# Shield.net
KiCad netlist of a schematic drawn in EAGLE
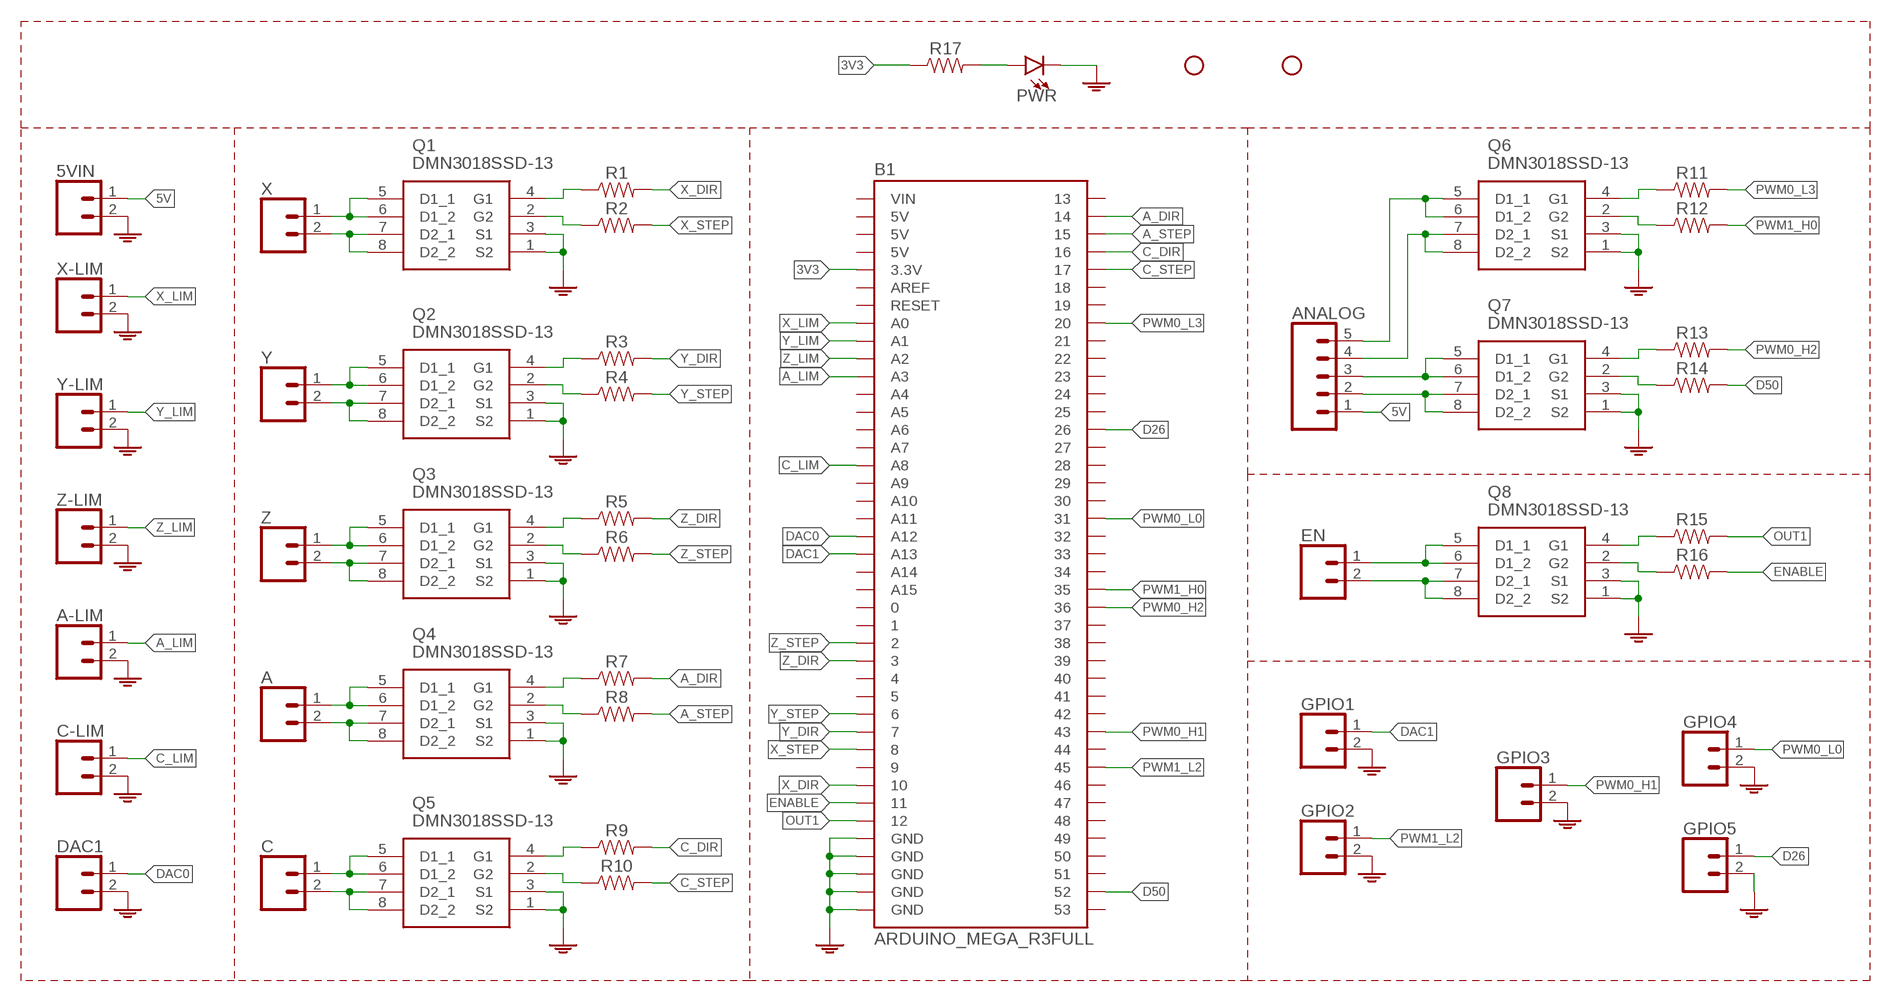
[diagram p0: schematic, sheet 1]

(export (version "E")
  (design (tool "Eeschema 10.0.6"))
  (components
    (comp (ref "5VIN")
      (value "2P-SCREWTERMINAL-PLUGABLE")
      (footprint "eagle-import:SCREWTERMINAL-3.5MM-2_LOCK")
      (libsource (lib "eagle-import") (part "2P-SCREWTERMINAL-PLUGABLE"))
    )
    (comp (ref "A")
      (value "2P-SCREWTERMINAL-PLUGABLE")
      (footprint "eagle-import:SCREWTERMINAL-3.5MM-2_LOCK")
      (libsource (lib "eagle-import") (part "2P-SCREWTERMINAL-PLUGABLE"))
    )
    (comp (ref "A-LIM")
      (value "2P-SCREWTERMINAL-PLUGABLE")
      (footprint "eagle-import:SCREWTERMINAL-3.5MM-2_LOCK")
      (libsource (lib "eagle-import") (part "2P-SCREWTERMINAL-PLUGABLE"))
    )
    (comp (ref "ANALOG")
      (value "JST-XH-5P")
      (footprint "eagle-import:JST-XH-5P")
      (libsource (lib "eagle-import") (part "JST-XH-5P"))
    )
    (comp (ref "B1")
      (value "ARDUINO_MEGA_R3FULL")
      (footprint "eagle-import:ARDUINO_MEGA")
      (libsource (lib "eagle-import") (part "ARDUINO_MEGA_R3FULL"))
    )
    (comp (ref "C")
      (value "2P-SCREWTERMINAL-PLUGABLE")
      (footprint "eagle-import:SCREWTERMINAL-3.5MM-2_LOCK")
      (libsource (lib "eagle-import") (part "2P-SCREWTERMINAL-PLUGABLE"))
    )
    (comp (ref "C-LIM")
      (value "2P-SCREWTERMINAL-PLUGABLE")
      (footprint "eagle-import:SCREWTERMINAL-3.5MM-2_LOCK")
      (libsource (lib "eagle-import") (part "2P-SCREWTERMINAL-PLUGABLE"))
    )
    (comp (ref "DAC1")
      (value "2P-SCREWTERMINAL-PLUGABLE")
      (footprint "eagle-import:SCREWTERMINAL-3.5MM-2_LOCK")
      (libsource (lib "eagle-import") (part "2P-SCREWTERMINAL-PLUGABLE"))
    )
    (comp (ref "EN")
      (value "2P-SCREWTERMINAL-PLUGABLE")
      (footprint "eagle-import:SCREWTERMINAL-3.5MM-2_LOCK")
      (libsource (lib "eagle-import") (part "2P-SCREWTERMINAL-PLUGABLE"))
    )
    (comp (ref "GPIO1")
      (value "2P-SCREWTERMINAL-PLUGABLE")
      (footprint "eagle-import:SCREWTERMINAL-3.5MM-2_LOCK")
      (libsource (lib "eagle-import") (part "2P-SCREWTERMINAL-PLUGABLE"))
    )
    (comp (ref "GPIO2")
      (value "2P-SCREWTERMINAL-PLUGABLE")
      (footprint "eagle-import:SCREWTERMINAL-3.5MM-2_LOCK")
      (libsource (lib "eagle-import") (part "2P-SCREWTERMINAL-PLUGABLE"))
    )
    (comp (ref "GPIO3")
      (value "2P-SCREWTERMINAL-PLUGABLE")
      (footprint "eagle-import:SCREWTERMINAL-3.5MM-2_LOCK")
      (libsource (lib "eagle-import") (part "2P-SCREWTERMINAL-PLUGABLE"))
    )
    (comp (ref "GPIO4")
      (value "2P-SCREWTERMINAL-PLUGABLE")
      (footprint "eagle-import:SCREWTERMINAL-3.5MM-2_LOCK")
      (libsource (lib "eagle-import") (part "2P-SCREWTERMINAL-PLUGABLE"))
    )
    (comp (ref "GPIO5")
      (value "2P-SCREWTERMINAL-PLUGABLE")
      (footprint "eagle-import:SCREWTERMINAL-3.5MM-2_LOCK")
      (libsource (lib "eagle-import") (part "2P-SCREWTERMINAL-PLUGABLE"))
    )
    (comp (ref "H1")
      (value "STAND-OFF")
      (footprint "eagle-import:STAND-OFF")
      (libsource (lib "eagle-import") (part "STAND-OFF"))
    )
    (comp (ref "H2")
      (value "STAND-OFF")
      (footprint "eagle-import:STAND-OFF")
      (libsource (lib "eagle-import") (part "STAND-OFF"))
    )
    (comp (ref "PWR")
      (value "LED-1206")
      (footprint "eagle-import:LED_1206")
      (libsource (lib "eagle-import") (part "LED-1206"))
    )
    (comp (ref "Q1")
      (value "DMN3018SSD-13")
      (footprint "eagle-import:SOIC127P600X175-8N")
      (fields (field (name "MOUSER_PART_NUMBER") "621-DMN3018SSD-13"))
      (libsource (lib "eagle-import") (part "DMN3018SSD-13"))
    )
    (comp (ref "Q2")
      (value "DMN3018SSD-13")
      (footprint "eagle-import:SOIC127P600X175-8N")
      (fields (field (name "MOUSER_PART_NUMBER") "621-DMN3018SSD-13"))
      (libsource (lib "eagle-import") (part "DMN3018SSD-13"))
    )
    (comp (ref "Q3")
      (value "DMN3018SSD-13")
      (footprint "eagle-import:SOIC127P600X175-8N")
      (fields (field (name "MOUSER_PART_NUMBER") "621-DMN3018SSD-13"))
      (libsource (lib "eagle-import") (part "DMN3018SSD-13"))
    )
    (comp (ref "Q4")
      (value "DMN3018SSD-13")
      (footprint "eagle-import:SOIC127P600X175-8N")
      (fields (field (name "MOUSER_PART_NUMBER") "621-DMN3018SSD-13"))
      (libsource (lib "eagle-import") (part "DMN3018SSD-13"))
    )
    (comp (ref "Q5")
      (value "DMN3018SSD-13")
      (footprint "eagle-import:SOIC127P600X175-8N")
      (fields (field (name "MOUSER_PART_NUMBER") "621-DMN3018SSD-13"))
      (libsource (lib "eagle-import") (part "DMN3018SSD-13"))
    )
    (comp (ref "Q6")
      (value "DMN3018SSD-13")
      (footprint "eagle-import:SOIC127P600X175-8N")
      (fields (field (name "MOUSER_PART_NUMBER") "621-DMN3018SSD-13"))
      (libsource (lib "eagle-import") (part "DMN3018SSD-13"))
    )
    (comp (ref "Q7")
      (value "DMN3018SSD-13")
      (footprint "eagle-import:SOIC127P600X175-8N")
      (fields (field (name "MOUSER_PART_NUMBER") "621-DMN3018SSD-13"))
      (libsource (lib "eagle-import") (part "DMN3018SSD-13"))
    )
    (comp (ref "Q8")
      (value "DMN3018SSD-13")
      (footprint "eagle-import:SOIC127P600X175-8N")
      (fields (field (name "MOUSER_PART_NUMBER") "621-DMN3018SSD-13"))
      (libsource (lib "eagle-import") (part "DMN3018SSD-13"))
    )
    (comp (ref "R1")
      (value "RESISTOR-SMD-1206")
      (footprint "eagle-import:RES_1206")
      (libsource (lib "eagle-import") (part "RESISTOR-SMD-1206"))
    )
    (comp (ref "R2")
      (value "RESISTOR-SMD-1206")
      (footprint "eagle-import:RES_1206")
      (libsource (lib "eagle-import") (part "RESISTOR-SMD-1206"))
    )
    (comp (ref "R3")
      (value "RESISTOR-SMD-1206")
      (footprint "eagle-import:RES_1206")
      (libsource (lib "eagle-import") (part "RESISTOR-SMD-1206"))
    )
    (comp (ref "R4")
      (value "RESISTOR-SMD-1206")
      (footprint "eagle-import:RES_1206")
      (libsource (lib "eagle-import") (part "RESISTOR-SMD-1206"))
    )
    (comp (ref "R5")
      (value "RESISTOR-SMD-1206")
      (footprint "eagle-import:RES_1206")
      (libsource (lib "eagle-import") (part "RESISTOR-SMD-1206"))
    )
    (comp (ref "R6")
      (value "RESISTOR-SMD-1206")
      (footprint "eagle-import:RES_1206")
      (libsource (lib "eagle-import") (part "RESISTOR-SMD-1206"))
    )
    (comp (ref "R7")
      (value "RESISTOR-SMD-1206")
      (footprint "eagle-import:RES_1206")
      (libsource (lib "eagle-import") (part "RESISTOR-SMD-1206"))
    )
    (comp (ref "R8")
      (value "RESISTOR-SMD-1206")
      (footprint "eagle-import:RES_1206")
      (libsource (lib "eagle-import") (part "RESISTOR-SMD-1206"))
    )
    (comp (ref "R9")
      (value "RESISTOR-SMD-1206")
      (footprint "eagle-import:RES_1206")
      (libsource (lib "eagle-import") (part "RESISTOR-SMD-1206"))
    )
    (comp (ref "R10")
      (value "RESISTOR-SMD-1206")
      (footprint "eagle-import:RES_1206")
      (libsource (lib "eagle-import") (part "RESISTOR-SMD-1206"))
    )
    (comp (ref "R11")
      (value "RESISTOR-SMD-1206")
      (footprint "eagle-import:RES_1206")
      (libsource (lib "eagle-import") (part "RESISTOR-SMD-1206"))
    )
    (comp (ref "R12")
      (value "RESISTOR-SMD-1206")
      (footprint "eagle-import:RES_1206")
      (libsource (lib "eagle-import") (part "RESISTOR-SMD-1206"))
    )
    (comp (ref "R13")
      (value "RESISTOR-SMD-1206")
      (footprint "eagle-import:RES_1206")
      (libsource (lib "eagle-import") (part "RESISTOR-SMD-1206"))
    )
    (comp (ref "R14")
      (value "RESISTOR-SMD-1206")
      (footprint "eagle-import:RES_1206")
      (libsource (lib "eagle-import") (part "RESISTOR-SMD-1206"))
    )
    (comp (ref "R15")
      (value "RESISTOR-SMD-1206")
      (footprint "eagle-import:RES_1206")
      (libsource (lib "eagle-import") (part "RESISTOR-SMD-1206"))
    )
    (comp (ref "R16")
      (value "RESISTOR-SMD-1206")
      (footprint "eagle-import:RES_1206")
      (libsource (lib "eagle-import") (part "RESISTOR-SMD-1206"))
    )
    (comp (ref "R17")
      (value "RESISTOR-SMD-1206")
      (footprint "eagle-import:RES_1206")
      (libsource (lib "eagle-import") (part "RESISTOR-SMD-1206"))
    )
    (comp (ref "X")
      (value "2P-SCREWTERMINAL-PLUGABLE")
      (footprint "eagle-import:SCREWTERMINAL-3.5MM-2_LOCK")
      (libsource (lib "eagle-import") (part "2P-SCREWTERMINAL-PLUGABLE"))
    )
    (comp (ref "X-LIM")
      (value "2P-SCREWTERMINAL-PLUGABLE")
      (footprint "eagle-import:SCREWTERMINAL-3.5MM-2_LOCK")
      (libsource (lib "eagle-import") (part "2P-SCREWTERMINAL-PLUGABLE"))
    )
    (comp (ref "Y")
      (value "2P-SCREWTERMINAL-PLUGABLE")
      (footprint "eagle-import:SCREWTERMINAL-3.5MM-2_LOCK")
      (libsource (lib "eagle-import") (part "2P-SCREWTERMINAL-PLUGABLE"))
    )
    (comp (ref "Y-LIM")
      (value "2P-SCREWTERMINAL-PLUGABLE")
      (footprint "eagle-import:SCREWTERMINAL-3.5MM-2_LOCK")
      (libsource (lib "eagle-import") (part "2P-SCREWTERMINAL-PLUGABLE"))
    )
    (comp (ref "Z")
      (value "2P-SCREWTERMINAL-PLUGABLE")
      (footprint "eagle-import:SCREWTERMINAL-3.5MM-2_LOCK")
      (libsource (lib "eagle-import") (part "2P-SCREWTERMINAL-PLUGABLE"))
    )
    (comp (ref "Z-LIM")
      (value "2P-SCREWTERMINAL-PLUGABLE")
      (footprint "eagle-import:SCREWTERMINAL-3.5MM-2_LOCK")
      (libsource (lib "eagle-import") (part "2P-SCREWTERMINAL-PLUGABLE"))
    )
  )
  (nets
    (net (code "1") (name "3V3") (class "Default")
      (node (ref "B1") (pin "3.3V") (pinfunction "3.3V_3.3V") (pintype "bidirectional"))
      (node (ref "R17") (pin "1") (pinfunction "1_1") (pintype "passive"))
    )
    (net (code "2") (name "5V") (class "Default")
      (node (ref "5VIN") (pin "1") (pinfunction "1_1") (pintype "passive"))
      (node (ref "ANALOG") (pin "1") (pinfunction "1_1") (pintype "passive"))
    )
    (net (code "3") (name "A_DIR") (class "Default")
      (node (ref "B1") (pin "14") (pinfunction "14_14") (pintype "bidirectional"))
      (node (ref "R7") (pin "2") (pinfunction "2_2") (pintype "passive"))
    )
    (net (code "4") (name "A_LIM") (class "Default")
      (node (ref "A-LIM") (pin "1") (pinfunction "1_1") (pintype "passive"))
      (node (ref "B1") (pin "A3") (pinfunction "A3_A3") (pintype "bidirectional"))
    )
    (net (code "5") (name "A_STEP") (class "Default")
      (node (ref "B1") (pin "15") (pinfunction "15_15") (pintype "bidirectional"))
      (node (ref "R8") (pin "2") (pinfunction "2_2") (pintype "passive"))
    )
    (net (code "6") (name "C_DIR") (class "Default")
      (node (ref "B1") (pin "16") (pinfunction "16_16") (pintype "bidirectional"))
      (node (ref "R9") (pin "2") (pinfunction "2_2") (pintype "passive"))
    )
    (net (code "7") (name "C_LIM") (class "Default")
      (node (ref "B1") (pin "A8") (pinfunction "A8_A8") (pintype "bidirectional"))
      (node (ref "C-LIM") (pin "1") (pinfunction "1_1") (pintype "passive"))
    )
    (net (code "8") (name "C_STEP") (class "Default")
      (node (ref "B1") (pin "17") (pinfunction "17_17") (pintype "bidirectional"))
      (node (ref "R10") (pin "2") (pinfunction "2_2") (pintype "passive"))
    )
    (net (code "9") (name "D26") (class "Default")
      (node (ref "B1") (pin "26") (pinfunction "26_26") (pintype "bidirectional"))
      (node (ref "GPIO5") (pin "1") (pinfunction "1_1") (pintype "passive"))
    )
    (net (code "10") (name "D50") (class "Default")
      (node (ref "B1") (pin "52") (pinfunction "52_52") (pintype "bidirectional"))
      (node (ref "R14") (pin "2") (pinfunction "2_2") (pintype "passive"))
    )
    (net (code "11") (name "DAC0") (class "Default")
      (node (ref "B1") (pin "A12") (pinfunction "A12_A12") (pintype "bidirectional"))
      (node (ref "DAC1") (pin "1") (pinfunction "1_1") (pintype "passive"))
    )
    (net (code "12") (name "DAC1") (class "Default")
      (node (ref "B1") (pin "A13") (pinfunction "A13_A13") (pintype "bidirectional"))
      (node (ref "GPIO1") (pin "1") (pinfunction "1_1") (pintype "passive"))
    )
    (net (code "13") (name "ENABLE") (class "Default")
      (node (ref "B1") (pin "11") (pinfunction "11_11") (pintype "bidirectional"))
      (node (ref "R16") (pin "2") (pinfunction "2_2") (pintype "passive"))
    )
    (net (code "14") (name "GND") (class "Default")
      (node (ref "5VIN") (pin "2") (pinfunction "2_2") (pintype "passive"))
      (node (ref "A-LIM") (pin "2") (pinfunction "2_2") (pintype "passive"))
      (node (ref "B1") (pin "GND@0") (pinfunction "GND_GND@0") (pintype "bidirectional"))
      (node (ref "B1") (pin "GND@1") (pinfunction "GND_GND@1") (pintype "bidirectional"))
      (node (ref "B1") (pin "GND@2") (pinfunction "GND_GND@2") (pintype "bidirectional"))
      (node (ref "B1") (pin "GND@3") (pinfunction "GND_GND@3") (pintype "bidirectional"))
      (node (ref "B1") (pin "GND@4") (pinfunction "GND_GND@4") (pintype "bidirectional"))
      (node (ref "C-LIM") (pin "2") (pinfunction "2_2") (pintype "passive"))
      (node (ref "DAC1") (pin "2") (pinfunction "2_2") (pintype "passive"))
      (node (ref "GPIO1") (pin "2") (pinfunction "2_2") (pintype "passive"))
      (node (ref "GPIO2") (pin "2") (pinfunction "2_2") (pintype "passive"))
      (node (ref "GPIO3") (pin "2") (pinfunction "2_2") (pintype "passive"))
      (node (ref "GPIO4") (pin "2") (pinfunction "2_2") (pintype "passive"))
      (node (ref "GPIO5") (pin "2") (pinfunction "2_2") (pintype "passive"))
      (node (ref "PWR") (pin "C") (pinfunction "C_C") (pintype "passive"))
      (node (ref "Q1") (pin "1") (pinfunction "S2_1") (pintype "bidirectional"))
      (node (ref "Q1") (pin "3") (pinfunction "S1_3") (pintype "bidirectional"))
      (node (ref "Q2") (pin "1") (pinfunction "S2_1") (pintype "bidirectional"))
      (node (ref "Q2") (pin "3") (pinfunction "S1_3") (pintype "bidirectional"))
      (node (ref "Q3") (pin "1") (pinfunction "S2_1") (pintype "bidirectional"))
      (node (ref "Q3") (pin "3") (pinfunction "S1_3") (pintype "bidirectional"))
      (node (ref "Q4") (pin "1") (pinfunction "S2_1") (pintype "bidirectional"))
      (node (ref "Q4") (pin "3") (pinfunction "S1_3") (pintype "bidirectional"))
      (node (ref "Q5") (pin "1") (pinfunction "S2_1") (pintype "bidirectional"))
      (node (ref "Q5") (pin "3") (pinfunction "S1_3") (pintype "bidirectional"))
      (node (ref "Q6") (pin "1") (pinfunction "S2_1") (pintype "bidirectional"))
      (node (ref "Q6") (pin "3") (pinfunction "S1_3") (pintype "bidirectional"))
      (node (ref "Q7") (pin "1") (pinfunction "S2_1") (pintype "bidirectional"))
      (node (ref "Q7") (pin "3") (pinfunction "S1_3") (pintype "bidirectional"))
      (node (ref "Q8") (pin "1") (pinfunction "S2_1") (pintype "bidirectional"))
      (node (ref "Q8") (pin "3") (pinfunction "S1_3") (pintype "bidirectional"))
      (node (ref "X-LIM") (pin "2") (pinfunction "2_2") (pintype "passive"))
      (node (ref "Y-LIM") (pin "2") (pinfunction "2_2") (pintype "passive"))
      (node (ref "Z-LIM") (pin "2") (pinfunction "2_2") (pintype "passive"))
    )
    (net (code "15") (name "Net-(PWR-PadA)") (class "Default")
      (node (ref "PWR") (pin "A") (pinfunction "A_A") (pintype "passive"))
      (node (ref "R17") (pin "2") (pinfunction "2_2") (pintype "passive"))
    )
    (net (code "16") (name "Net-(Q1-D1_1)") (class "Default")
      (node (ref "Q1") (pin "5") (pinfunction "D1_1_5") (pintype "bidirectional"))
      (node (ref "Q1") (pin "6") (pinfunction "D1_2_6") (pintype "bidirectional"))
      (node (ref "X") (pin "1") (pinfunction "1_1") (pintype "passive"))
    )
    (net (code "17") (name "Net-(Q1-D2_1)") (class "Default")
      (node (ref "Q1") (pin "7") (pinfunction "D2_1_7") (pintype "bidirectional"))
      (node (ref "Q1") (pin "8") (pinfunction "D2_2_8") (pintype "bidirectional"))
      (node (ref "X") (pin "2") (pinfunction "2_2") (pintype "passive"))
    )
    (net (code "18") (name "Net-(Q1-G1)") (class "Default")
      (node (ref "Q1") (pin "4") (pinfunction "G1_4") (pintype "bidirectional"))
      (node (ref "R1") (pin "1") (pinfunction "1_1") (pintype "passive"))
    )
    (net (code "19") (name "Net-(Q1-G2)") (class "Default")
      (node (ref "Q1") (pin "2") (pinfunction "G2_2") (pintype "bidirectional"))
      (node (ref "R2") (pin "1") (pinfunction "1_1") (pintype "passive"))
    )
    (net (code "20") (name "Net-(Q2-D1_1)") (class "Default")
      (node (ref "Q2") (pin "5") (pinfunction "D1_1_5") (pintype "bidirectional"))
      (node (ref "Q2") (pin "6") (pinfunction "D1_2_6") (pintype "bidirectional"))
      (node (ref "Y") (pin "1") (pinfunction "1_1") (pintype "passive"))
    )
    (net (code "21") (name "Net-(Q2-D2_1)") (class "Default")
      (node (ref "Q2") (pin "7") (pinfunction "D2_1_7") (pintype "bidirectional"))
      (node (ref "Q2") (pin "8") (pinfunction "D2_2_8") (pintype "bidirectional"))
      (node (ref "Y") (pin "2") (pinfunction "2_2") (pintype "passive"))
    )
    (net (code "22") (name "Net-(Q2-G1)") (class "Default")
      (node (ref "Q2") (pin "4") (pinfunction "G1_4") (pintype "bidirectional"))
      (node (ref "R3") (pin "1") (pinfunction "1_1") (pintype "passive"))
    )
    (net (code "23") (name "Net-(Q2-G2)") (class "Default")
      (node (ref "Q2") (pin "2") (pinfunction "G2_2") (pintype "bidirectional"))
      (node (ref "R4") (pin "1") (pinfunction "1_1") (pintype "passive"))
    )
    (net (code "24") (name "Net-(Q3-D1_1)") (class "Default")
      (node (ref "Q3") (pin "5") (pinfunction "D1_1_5") (pintype "bidirectional"))
      (node (ref "Q3") (pin "6") (pinfunction "D1_2_6") (pintype "bidirectional"))
      (node (ref "Z") (pin "1") (pinfunction "1_1") (pintype "passive"))
    )
    (net (code "25") (name "Net-(Q3-D2_1)") (class "Default")
      (node (ref "Q3") (pin "7") (pinfunction "D2_1_7") (pintype "bidirectional"))
      (node (ref "Q3") (pin "8") (pinfunction "D2_2_8") (pintype "bidirectional"))
      (node (ref "Z") (pin "2") (pinfunction "2_2") (pintype "passive"))
    )
    (net (code "26") (name "Net-(Q3-G1)") (class "Default")
      (node (ref "Q3") (pin "4") (pinfunction "G1_4") (pintype "bidirectional"))
      (node (ref "R5") (pin "1") (pinfunction "1_1") (pintype "passive"))
    )
    (net (code "27") (name "Net-(Q3-G2)") (class "Default")
      (node (ref "Q3") (pin "2") (pinfunction "G2_2") (pintype "bidirectional"))
      (node (ref "R6") (pin "1") (pinfunction "1_1") (pintype "passive"))
    )
    (net (code "28") (name "Net-(Q4-D1_1)") (class "Default")
      (node (ref "A") (pin "1") (pinfunction "1_1") (pintype "passive"))
      (node (ref "Q4") (pin "5") (pinfunction "D1_1_5") (pintype "bidirectional"))
      (node (ref "Q4") (pin "6") (pinfunction "D1_2_6") (pintype "bidirectional"))
    )
    (net (code "29") (name "Net-(Q4-D2_1)") (class "Default")
      (node (ref "A") (pin "2") (pinfunction "2_2") (pintype "passive"))
      (node (ref "Q4") (pin "7") (pinfunction "D2_1_7") (pintype "bidirectional"))
      (node (ref "Q4") (pin "8") (pinfunction "D2_2_8") (pintype "bidirectional"))
    )
    (net (code "30") (name "Net-(Q4-G1)") (class "Default")
      (node (ref "Q4") (pin "4") (pinfunction "G1_4") (pintype "bidirectional"))
      (node (ref "R7") (pin "1") (pinfunction "1_1") (pintype "passive"))
    )
    (net (code "31") (name "Net-(Q4-G2)") (class "Default")
      (node (ref "Q4") (pin "2") (pinfunction "G2_2") (pintype "bidirectional"))
      (node (ref "R8") (pin "1") (pinfunction "1_1") (pintype "passive"))
    )
    (net (code "32") (name "Net-(Q5-D1_1)") (class "Default")
      (node (ref "C") (pin "1") (pinfunction "1_1") (pintype "passive"))
      (node (ref "Q5") (pin "5") (pinfunction "D1_1_5") (pintype "bidirectional"))
      (node (ref "Q5") (pin "6") (pinfunction "D1_2_6") (pintype "bidirectional"))
    )
    (net (code "33") (name "Net-(Q5-D2_1)") (class "Default")
      (node (ref "C") (pin "2") (pinfunction "2_2") (pintype "passive"))
      (node (ref "Q5") (pin "7") (pinfunction "D2_1_7") (pintype "bidirectional"))
      (node (ref "Q5") (pin "8") (pinfunction "D2_2_8") (pintype "bidirectional"))
    )
    (net (code "34") (name "Net-(Q5-G1)") (class "Default")
      (node (ref "Q5") (pin "4") (pinfunction "G1_4") (pintype "bidirectional"))
      (node (ref "R9") (pin "1") (pinfunction "1_1") (pintype "passive"))
    )
    (net (code "35") (name "Net-(Q5-G2)") (class "Default")
      (node (ref "Q5") (pin "2") (pinfunction "G2_2") (pintype "bidirectional"))
      (node (ref "R10") (pin "1") (pinfunction "1_1") (pintype "passive"))
    )
    (net (code "36") (name "Net-(Q6-D1_1)") (class "Default")
      (node (ref "ANALOG") (pin "5") (pinfunction "5_5") (pintype "passive"))
      (node (ref "Q6") (pin "5") (pinfunction "D1_1_5") (pintype "bidirectional"))
      (node (ref "Q6") (pin "6") (pinfunction "D1_2_6") (pintype "bidirectional"))
    )
    (net (code "37") (name "Net-(Q6-D2_1)") (class "Default")
      (node (ref "ANALOG") (pin "4") (pinfunction "4_4") (pintype "passive"))
      (node (ref "Q6") (pin "7") (pinfunction "D2_1_7") (pintype "bidirectional"))
      (node (ref "Q6") (pin "8") (pinfunction "D2_2_8") (pintype "bidirectional"))
    )
    (net (code "38") (name "Net-(Q6-G1)") (class "Default")
      (node (ref "Q6") (pin "4") (pinfunction "G1_4") (pintype "bidirectional"))
      (node (ref "R11") (pin "1") (pinfunction "1_1") (pintype "passive"))
    )
    (net (code "39") (name "Net-(Q6-G2)") (class "Default")
      (node (ref "Q6") (pin "2") (pinfunction "G2_2") (pintype "bidirectional"))
      (node (ref "R12") (pin "1") (pinfunction "1_1") (pintype "passive"))
    )
    (net (code "40") (name "Net-(Q7-D1_1)") (class "Default")
      (node (ref "ANALOG") (pin "3") (pinfunction "3_3") (pintype "passive"))
      (node (ref "Q7") (pin "5") (pinfunction "D1_1_5") (pintype "bidirectional"))
      (node (ref "Q7") (pin "6") (pinfunction "D1_2_6") (pintype "bidirectional"))
    )
    (net (code "41") (name "Net-(Q7-D2_1)") (class "Default")
      (node (ref "ANALOG") (pin "2") (pinfunction "2_2") (pintype "passive"))
      (node (ref "Q7") (pin "7") (pinfunction "D2_1_7") (pintype "bidirectional"))
      (node (ref "Q7") (pin "8") (pinfunction "D2_2_8") (pintype "bidirectional"))
    )
    (net (code "42") (name "Net-(Q7-G1)") (class "Default")
      (node (ref "Q7") (pin "4") (pinfunction "G1_4") (pintype "bidirectional"))
      (node (ref "R13") (pin "1") (pinfunction "1_1") (pintype "passive"))
    )
    (net (code "43") (name "Net-(Q7-G2)") (class "Default")
      (node (ref "Q7") (pin "2") (pinfunction "G2_2") (pintype "bidirectional"))
      (node (ref "R14") (pin "1") (pinfunction "1_1") (pintype "passive"))
    )
    (net (code "44") (name "Net-(Q8-D1_1)") (class "Default")
      (node (ref "EN") (pin "1") (pinfunction "1_1") (pintype "passive"))
      (node (ref "Q8") (pin "5") (pinfunction "D1_1_5") (pintype "bidirectional"))
      (node (ref "Q8") (pin "6") (pinfunction "D1_2_6") (pintype "bidirectional"))
    )
    (net (code "45") (name "Net-(Q8-D2_1)") (class "Default")
      (node (ref "EN") (pin "2") (pinfunction "2_2") (pintype "passive"))
      (node (ref "Q8") (pin "7") (pinfunction "D2_1_7") (pintype "bidirectional"))
      (node (ref "Q8") (pin "8") (pinfunction "D2_2_8") (pintype "bidirectional"))
    )
    (net (code "46") (name "Net-(Q8-G1)") (class "Default")
      (node (ref "Q8") (pin "4") (pinfunction "G1_4") (pintype "bidirectional"))
      (node (ref "R15") (pin "1") (pinfunction "1_1") (pintype "passive"))
    )
    (net (code "47") (name "Net-(Q8-G2)") (class "Default")
      (node (ref "Q8") (pin "2") (pinfunction "G2_2") (pintype "bidirectional"))
      (node (ref "R16") (pin "1") (pinfunction "1_1") (pintype "passive"))
    )
    (net (code "48") (name "OUT1") (class "Default")
      (node (ref "B1") (pin "12") (pinfunction "12_12") (pintype "bidirectional"))
      (node (ref "R15") (pin "2") (pinfunction "2_2") (pintype "passive"))
    )
    (net (code "49") (name "PWM0_H1") (class "Default")
      (node (ref "B1") (pin "43") (pinfunction "43_43") (pintype "bidirectional"))
      (node (ref "GPIO3") (pin "1") (pinfunction "1_1") (pintype "passive"))
    )
    (net (code "50") (name "PWM0_H2") (class "Default")
      (node (ref "B1") (pin "36") (pinfunction "36_36") (pintype "bidirectional"))
      (node (ref "R13") (pin "2") (pinfunction "2_2") (pintype "passive"))
    )
    (net (code "51") (name "PWM0_L0") (class "Default")
      (node (ref "B1") (pin "31") (pinfunction "31_31") (pintype "bidirectional"))
      (node (ref "GPIO4") (pin "1") (pinfunction "1_1") (pintype "passive"))
    )
    (net (code "52") (name "PWM0_L3") (class "Default")
      (node (ref "B1") (pin "20") (pinfunction "20_20") (pintype "bidirectional"))
      (node (ref "R11") (pin "2") (pinfunction "2_2") (pintype "passive"))
    )
    (net (code "53") (name "PWM1_H0") (class "Default")
      (node (ref "B1") (pin "35") (pinfunction "35_35") (pintype "bidirectional"))
      (node (ref "R12") (pin "2") (pinfunction "2_2") (pintype "passive"))
    )
    (net (code "54") (name "PWM1_L2") (class "Default")
      (node (ref "B1") (pin "45") (pinfunction "45_45") (pintype "bidirectional"))
      (node (ref "GPIO2") (pin "1") (pinfunction "1_1") (pintype "passive"))
    )
    (net (code "55") (name "X_DIR") (class "Default")
      (node (ref "B1") (pin "10") (pinfunction "10_10") (pintype "bidirectional"))
      (node (ref "R1") (pin "2") (pinfunction "2_2") (pintype "passive"))
    )
    (net (code "56") (name "X_LIM") (class "Default")
      (node (ref "B1") (pin "A0") (pinfunction "A0_A0") (pintype "bidirectional"))
      (node (ref "X-LIM") (pin "1") (pinfunction "1_1") (pintype "passive"))
    )
    (net (code "57") (name "X_STEP") (class "Default")
      (node (ref "B1") (pin "8") (pinfunction "8_8") (pintype "bidirectional"))
      (node (ref "R2") (pin "2") (pinfunction "2_2") (pintype "passive"))
    )
    (net (code "58") (name "Y_DIR") (class "Default")
      (node (ref "B1") (pin "7") (pinfunction "7_7") (pintype "bidirectional"))
      (node (ref "R3") (pin "2") (pinfunction "2_2") (pintype "passive"))
    )
    (net (code "59") (name "Y_LIM") (class "Default")
      (node (ref "B1") (pin "A1") (pinfunction "A1_A1") (pintype "bidirectional"))
      (node (ref "Y-LIM") (pin "1") (pinfunction "1_1") (pintype "passive"))
    )
    (net (code "60") (name "Y_STEP") (class "Default")
      (node (ref "B1") (pin "6") (pinfunction "6_6") (pintype "bidirectional"))
      (node (ref "R4") (pin "2") (pinfunction "2_2") (pintype "passive"))
    )
    (net (code "61") (name "Z_DIR") (class "Default")
      (node (ref "B1") (pin "3") (pinfunction "3_3") (pintype "bidirectional"))
      (node (ref "R5") (pin "2") (pinfunction "2_2") (pintype "passive"))
    )
    (net (code "62") (name "Z_LIM") (class "Default")
      (node (ref "B1") (pin "A2") (pinfunction "A2_A2") (pintype "bidirectional"))
      (node (ref "Z-LIM") (pin "1") (pinfunction "1_1") (pintype "passive"))
    )
    (net (code "63") (name "Z_STEP") (class "Default")
      (node (ref "B1") (pin "2") (pinfunction "2_2") (pintype "bidirectional"))
      (node (ref "R6") (pin "2") (pinfunction "2_2") (pintype "passive"))
    )
    (net (code "64") (name "unconnected-(B1-5V-Pad5V@0)") (class "Default")
      (node (ref "B1") (pin "5V@0") (pinfunction "5V_5V@0") (pintype "bidirectional"))
    )
    (net (code "65") (name "unconnected-(B1-5V-Pad5V@1)") (class "Default")
      (node (ref "B1") (pin "5V@1") (pinfunction "5V_5V@1") (pintype "bidirectional"))
    )
    (net (code "66") (name "unconnected-(B1-5V-Pad5V@2)") (class "Default")
      (node (ref "B1") (pin "5V@2") (pinfunction "5V_5V@2") (pintype "bidirectional"))
    )
    (net (code "67") (name "unconnected-(B1-Pad0)") (class "Default")
      (node (ref "B1") (pin "0") (pinfunction "0_0") (pintype "bidirectional"))
    )
    (net (code "68") (name "unconnected-(B1-Pad1)") (class "Default")
      (node (ref "B1") (pin "1") (pinfunction "1_1") (pintype "bidirectional"))
    )
    (net (code "69") (name "unconnected-(B1-Pad4)") (class "Default")
      (node (ref "B1") (pin "4") (pinfunction "4_4") (pintype "bidirectional"))
    )
    (net (code "70") (name "unconnected-(B1-Pad5)") (class "Default")
      (node (ref "B1") (pin "5") (pinfunction "5_5") (pintype "bidirectional"))
    )
    (net (code "71") (name "unconnected-(B1-Pad9)") (class "Default")
      (node (ref "B1") (pin "9") (pinfunction "9_9") (pintype "bidirectional"))
    )
    (net (code "72") (name "unconnected-(B1-Pad13)") (class "Default")
      (node (ref "B1") (pin "13") (pinfunction "13_13") (pintype "bidirectional"))
    )
    (net (code "73") (name "unconnected-(B1-Pad18)") (class "Default")
      (node (ref "B1") (pin "18") (pinfunction "18_18") (pintype "bidirectional"))
    )
    (net (code "74") (name "unconnected-(B1-Pad19)") (class "Default")
      (node (ref "B1") (pin "19") (pinfunction "19_19") (pintype "bidirectional"))
    )
    (net (code "75") (name "unconnected-(B1-Pad21)") (class "Default")
      (node (ref "B1") (pin "21") (pinfunction "21_21") (pintype "bidirectional"))
    )
    (net (code "76") (name "unconnected-(B1-Pad22)") (class "Default")
      (node (ref "B1") (pin "22") (pinfunction "22_22") (pintype "bidirectional"))
    )
    (net (code "77") (name "unconnected-(B1-Pad23)") (class "Default")
      (node (ref "B1") (pin "23") (pinfunction "23_23") (pintype "bidirectional"))
    )
    (net (code "78") (name "unconnected-(B1-Pad24)") (class "Default")
      (node (ref "B1") (pin "24") (pinfunction "24_24") (pintype "bidirectional"))
    )
    (net (code "79") (name "unconnected-(B1-Pad25)") (class "Default")
      (node (ref "B1") (pin "25") (pinfunction "25_25") (pintype "bidirectional"))
    )
    (net (code "80") (name "unconnected-(B1-Pad27)") (class "Default")
      (node (ref "B1") (pin "27") (pinfunction "27_27") (pintype "bidirectional"))
    )
    (net (code "81") (name "unconnected-(B1-Pad28)") (class "Default")
      (node (ref "B1") (pin "28") (pinfunction "28_28") (pintype "bidirectional"))
    )
    (net (code "82") (name "unconnected-(B1-Pad29)") (class "Default")
      (node (ref "B1") (pin "29") (pinfunction "29_29") (pintype "bidirectional"))
    )
    (net (code "83") (name "unconnected-(B1-Pad30)") (class "Default")
      (node (ref "B1") (pin "30") (pinfunction "30_30") (pintype "bidirectional"))
    )
    (net (code "84") (name "unconnected-(B1-Pad32)") (class "Default")
      (node (ref "B1") (pin "32") (pinfunction "32_32") (pintype "bidirectional"))
    )
    (net (code "85") (name "unconnected-(B1-Pad33)") (class "Default")
      (node (ref "B1") (pin "33") (pinfunction "33_33") (pintype "bidirectional"))
    )
    (net (code "86") (name "unconnected-(B1-Pad34)") (class "Default")
      (node (ref "B1") (pin "34") (pinfunction "34_34") (pintype "bidirectional"))
    )
    (net (code "87") (name "unconnected-(B1-Pad37)") (class "Default")
      (node (ref "B1") (pin "37") (pinfunction "37_37") (pintype "bidirectional"))
    )
    (net (code "88") (name "unconnected-(B1-Pad38)") (class "Default")
      (node (ref "B1") (pin "38") (pinfunction "38_38") (pintype "bidirectional"))
    )
    (net (code "89") (name "unconnected-(B1-Pad39)") (class "Default")
      (node (ref "B1") (pin "39") (pinfunction "39_39") (pintype "bidirectional"))
    )
    (net (code "90") (name "unconnected-(B1-Pad40)") (class "Default")
      (node (ref "B1") (pin "40") (pinfunction "40_40") (pintype "bidirectional"))
    )
    (net (code "91") (name "unconnected-(B1-Pad41)") (class "Default")
      (node (ref "B1") (pin "41") (pinfunction "41_41") (pintype "bidirectional"))
    )
    (net (code "92") (name "unconnected-(B1-Pad42)") (class "Default")
      (node (ref "B1") (pin "42") (pinfunction "42_42") (pintype "bidirectional"))
    )
    (net (code "93") (name "unconnected-(B1-Pad44)") (class "Default")
      (node (ref "B1") (pin "44") (pinfunction "44_44") (pintype "bidirectional"))
    )
    (net (code "94") (name "unconnected-(B1-Pad46)") (class "Default")
      (node (ref "B1") (pin "46") (pinfunction "46_46") (pintype "bidirectional"))
    )
    (net (code "95") (name "unconnected-(B1-Pad47)") (class "Default")
      (node (ref "B1") (pin "47") (pinfunction "47_47") (pintype "bidirectional"))
    )
    (net (code "96") (name "unconnected-(B1-Pad48)") (class "Default")
      (node (ref "B1") (pin "48") (pinfunction "48_48") (pintype "bidirectional"))
    )
    (net (code "97") (name "unconnected-(B1-Pad49)") (class "Default")
      (node (ref "B1") (pin "49") (pinfunction "49_49") (pintype "bidirectional"))
    )
    (net (code "98") (name "unconnected-(B1-Pad50)") (class "Default")
      (node (ref "B1") (pin "50") (pinfunction "50_50") (pintype "bidirectional"))
    )
    (net (code "99") (name "unconnected-(B1-Pad51)") (class "Default")
      (node (ref "B1") (pin "51") (pinfunction "51_51") (pintype "bidirectional"))
    )
    (net (code "100") (name "unconnected-(B1-Pad53)") (class "Default")
      (node (ref "B1") (pin "53") (pinfunction "53_53") (pintype "bidirectional"))
    )
    (net (code "101") (name "unconnected-(B1-PadA4)") (class "Default")
      (node (ref "B1") (pin "A4") (pinfunction "A4_A4") (pintype "bidirectional"))
    )
    (net (code "102") (name "unconnected-(B1-PadA5)") (class "Default")
      (node (ref "B1") (pin "A5") (pinfunction "A5_A5") (pintype "bidirectional"))
    )
    (net (code "103") (name "unconnected-(B1-PadA6)") (class "Default")
      (node (ref "B1") (pin "A6") (pinfunction "A6_A6") (pintype "bidirectional"))
    )
    (net (code "104") (name "unconnected-(B1-PadA7)") (class "Default")
      (node (ref "B1") (pin "A7") (pinfunction "A7_A7") (pintype "bidirectional"))
    )
    (net (code "105") (name "unconnected-(B1-PadA9)") (class "Default")
      (node (ref "B1") (pin "A9") (pinfunction "A9_A9") (pintype "bidirectional"))
    )
    (net (code "106") (name "unconnected-(B1-PadA10)") (class "Default")
      (node (ref "B1") (pin "A10") (pinfunction "A10_A10") (pintype "bidirectional"))
    )
    (net (code "107") (name "unconnected-(B1-PadA11)") (class "Default")
      (node (ref "B1") (pin "A11") (pinfunction "A11_A11") (pintype "bidirectional"))
    )
    (net (code "108") (name "unconnected-(B1-PadA14)") (class "Default")
      (node (ref "B1") (pin "A14") (pinfunction "A14_A14") (pintype "bidirectional"))
    )
    (net (code "109") (name "unconnected-(B1-PadA15)") (class "Default")
      (node (ref "B1") (pin "A15") (pinfunction "A15_A15") (pintype "bidirectional"))
    )
    (net (code "110") (name "unconnected-(B1-PadAREF)") (class "Default")
      (node (ref "B1") (pin "AREF") (pinfunction "AREF_AREF") (pintype "bidirectional"))
    )
    (net (code "111") (name "unconnected-(B1-PadRESET)") (class "Default")
      (node (ref "B1") (pin "RESET") (pinfunction "RESET_RESET") (pintype "bidirectional"))
    )
    (net (code "112") (name "unconnected-(B1-PadVIN)") (class "Default")
      (node (ref "B1") (pin "VIN") (pinfunction "VIN_VIN") (pintype "bidirectional"))
    )
  )
)
